# PDB_Sheet1.net
KiCad netlist of a schematic drawn in Altium Designer
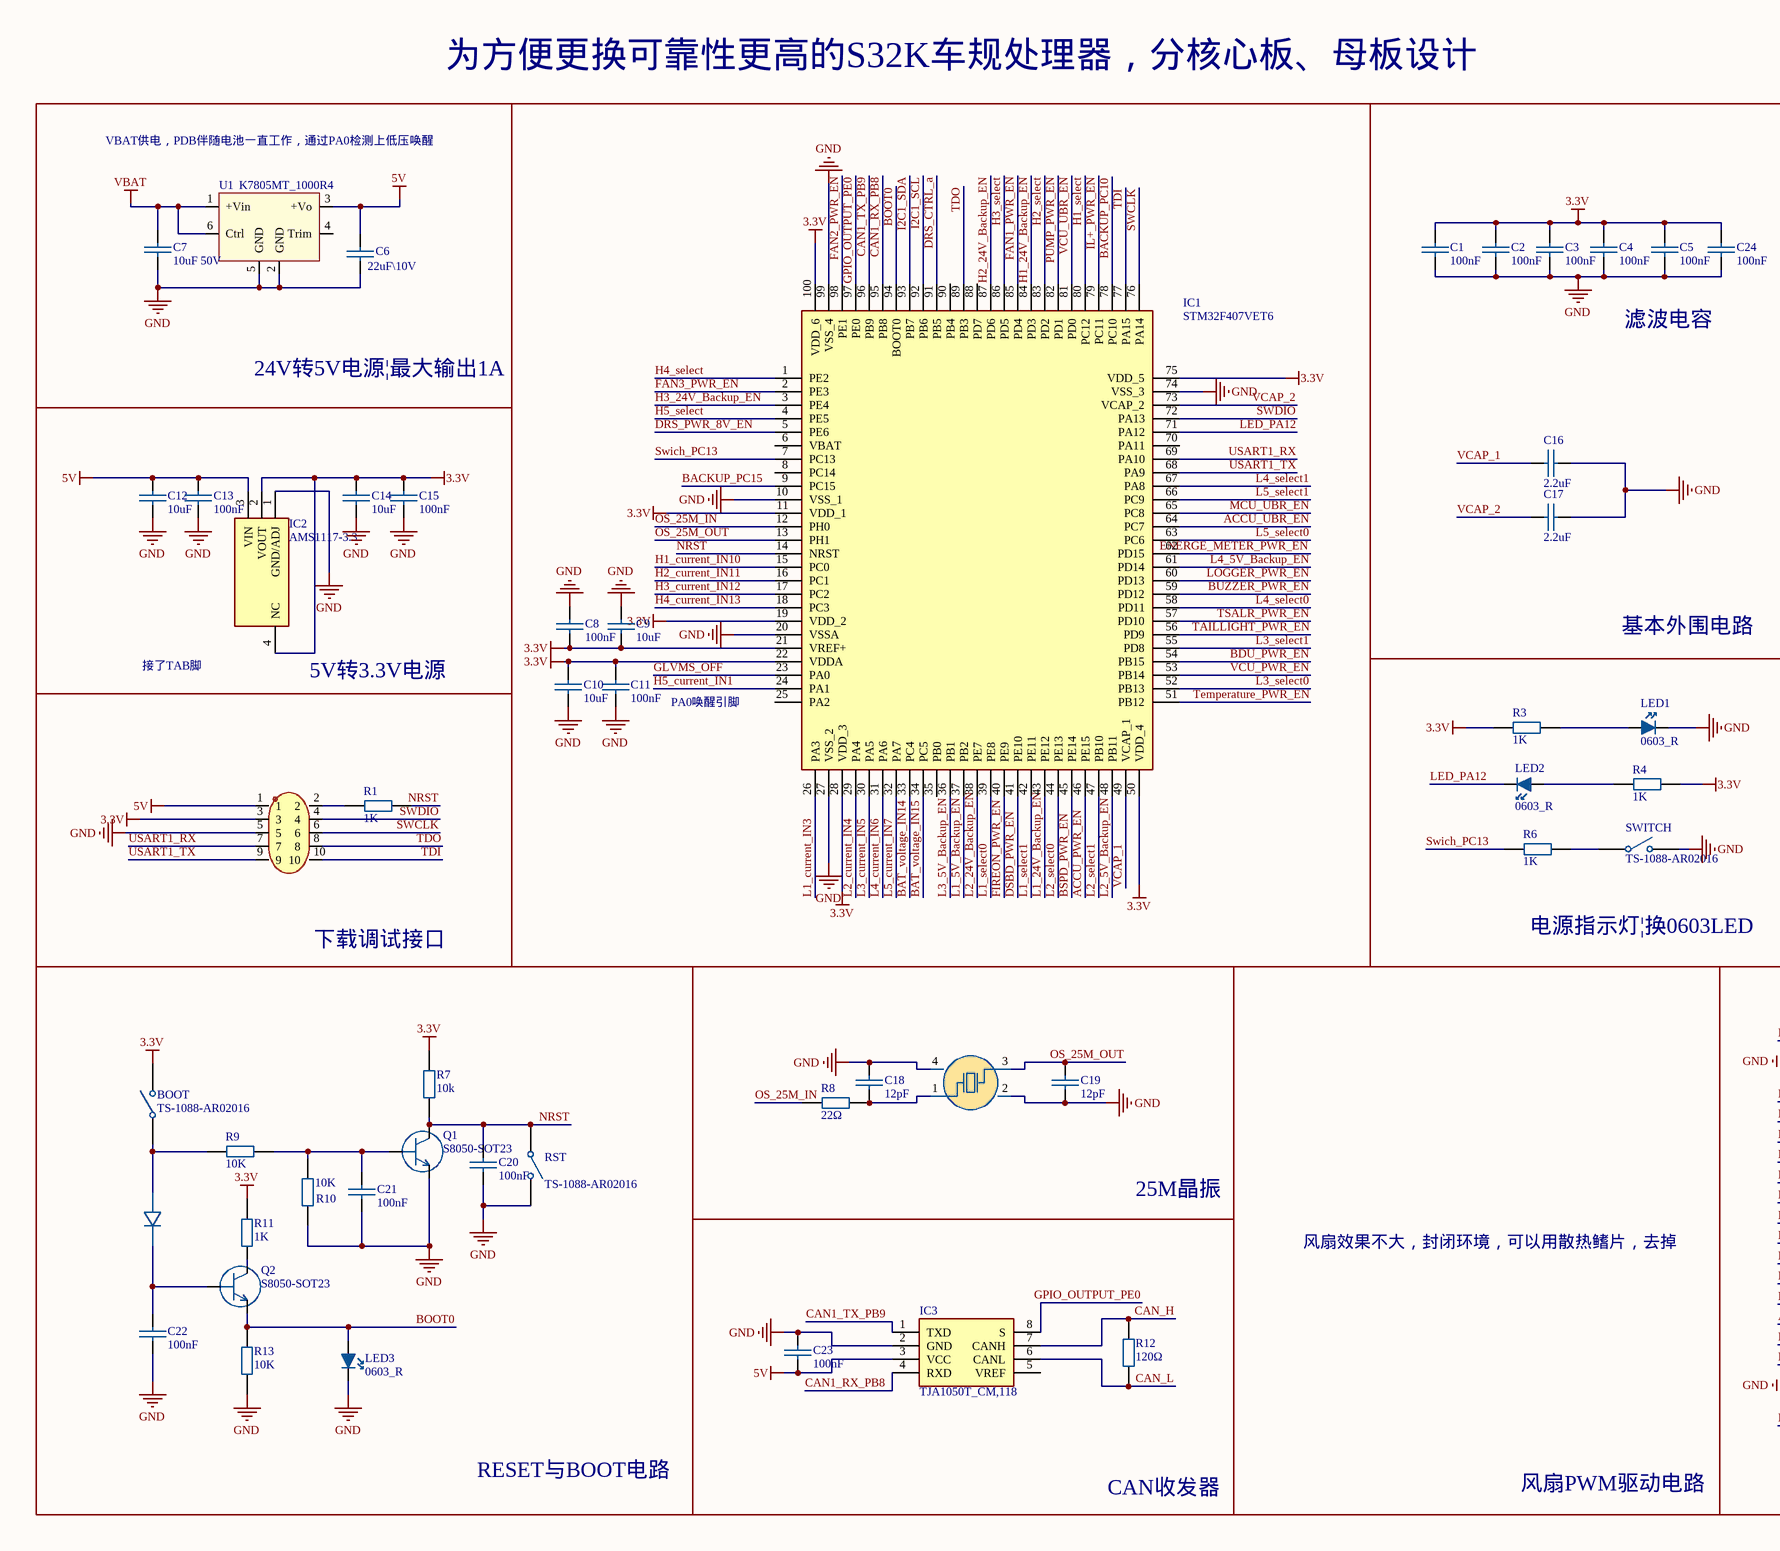
[diagram p0: PDB_Sheet1.SchDoc, left]
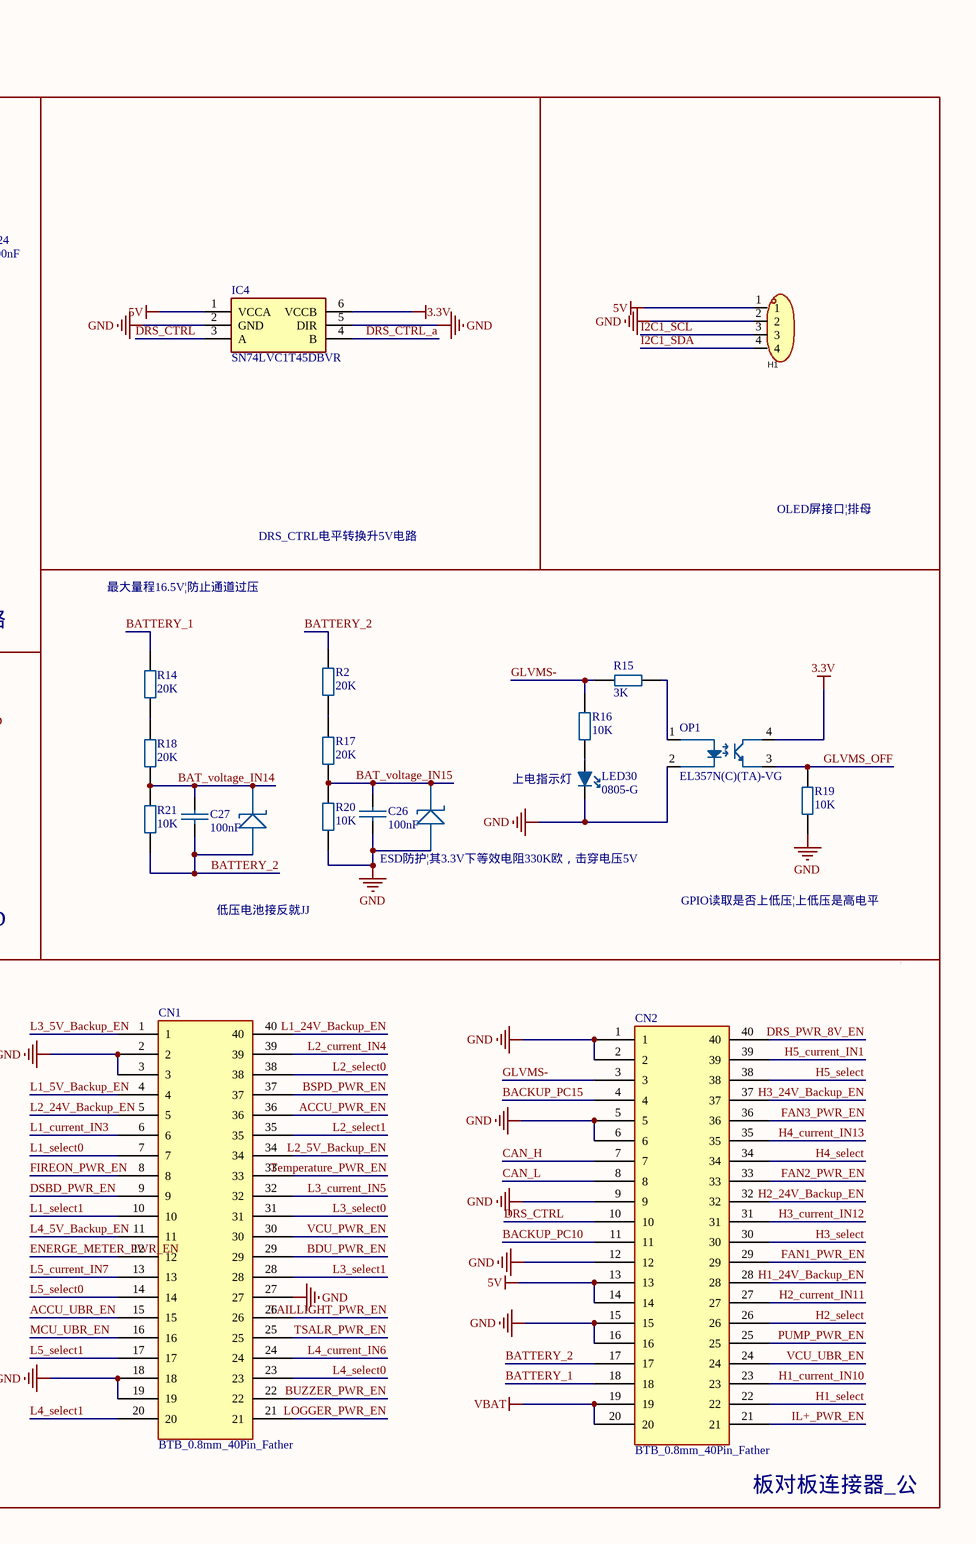
[diagram p1: PDB_Sheet1.SchDoc, right]

(export (version "E")
  (design (tool "Eeschema 10.0.6"))
  (components
    (comp (ref "BOOT")
      (value "TS-1088-AR02016")
      (footprint "SW-SMD_L3.9-W3.0-P4.45")
      (description "Switch")
      (libsource (lib "Switches") (part "TS-1088-AR02016"))
    )
    (comp (ref "C1")
      (value "100nF")
      (footprint "CAPC1608X08N__0603CAPUNPOLE")
      (description "Std MLCC Cap")
      (libsource (lib "ResistorCapacitorInductor") (part "SMD_MLCC"))
    )
    (comp (ref "C2")
      (value "100nF")
      (footprint "CAPC1608X08N__0603CAPUNPOLE")
      (description "Std MLCC Cap")
      (libsource (lib "ResistorCapacitorInductor") (part "SMD_MLCC"))
    )
    (comp (ref "C3")
      (value "100nF")
      (footprint "CAPC1608X08N__0603CAPUNPOLE")
      (description "Std MLCC Cap")
      (libsource (lib "ResistorCapacitorInductor") (part "SMD_MLCC"))
    )
    (comp (ref "C4")
      (value "100nF")
      (footprint "CAPC1608X08N__0603CAPUNPOLE")
      (description "Std MLCC Cap")
      (libsource (lib "ResistorCapacitorInductor") (part "SMD_MLCC"))
    )
    (comp (ref "C5")
      (value "100nF")
      (footprint "CAPC1608X08N__0603CAPUNPOLE")
      (description "Std MLCC Cap")
      (libsource (lib "ResistorCapacitorInductor") (part "SMD_MLCC"))
    )
    (comp (ref "C6")
      (value "22u~{F}10V")
      (footprint "CAPC1608X08N__0603CAPUNPOLE")
      (description "Std MLCC Cap")
      (libsource (lib "ResistorCapacitorInductor") (part "SMD_MLCC"))
    )
    (comp (ref "C7")
      (value "10uF 50V")
      (footprint "CAPC3216X16N_1206CAPUNPOLE")
      (description "Std MLCC Cap")
      (libsource (lib "ResistorCapacitorInductor") (part "SMD_MLCC"))
    )
    (comp (ref "C8")
      (value "100nF")
      (footprint "CAPC1608X08N__0603CAPUNPOLE")
      (description "Std MLCC Cap")
      (libsource (lib "ResistorCapacitorInductor") (part "SMD_MLCC"))
    )
    (comp (ref "C9")
      (value "10uF")
      (footprint "CAPC1608X08N__0603CAPUNPOLE")
      (description "Std MLCC Cap")
      (libsource (lib "ResistorCapacitorInductor") (part "SMD_MLCC"))
    )
    (comp (ref "C10")
      (value "10uF")
      (footprint "CAPC1608X08N__0603CAPUNPOLE")
      (description "Std MLCC Cap")
      (libsource (lib "ResistorCapacitorInductor") (part "SMD_MLCC"))
    )
    (comp (ref "C11")
      (value "100nF")
      (footprint "CAPC1608X08N__0603CAPUNPOLE")
      (description "Std MLCC Cap")
      (libsource (lib "ResistorCapacitorInductor") (part "SMD_MLCC"))
    )
    (comp (ref "C12")
      (value "10uF")
      (footprint "CAPC1608X08N__0603CAPUNPOLE")
      (description "Std MLCC Cap")
      (libsource (lib "ResistorCapacitorInductor") (part "SMD_MLCC"))
    )
    (comp (ref "C13")
      (value "100nF")
      (footprint "CAPC1608X08N__0603CAPUNPOLE")
      (description "Std MLCC Cap")
      (libsource (lib "ResistorCapacitorInductor") (part "SMD_MLCC"))
    )
    (comp (ref "C14")
      (value "10uF")
      (footprint "CAPC1608X08N__0603CAPUNPOLE")
      (description "Std MLCC Cap")
      (libsource (lib "ResistorCapacitorInductor") (part "SMD_MLCC"))
    )
    (comp (ref "C15")
      (value "100nF")
      (footprint "CAPC1608X08N__0603CAPUNPOLE")
      (description "Std MLCC Cap")
      (libsource (lib "ResistorCapacitorInductor") (part "SMD_MLCC"))
    )
    (comp (ref "C16")
      (value "2.2uF")
      (footprint "CAPC1608X08N__0603CAPUNPOLE")
      (description "Std MLCC Cap")
      (libsource (lib "ResistorCapacitorInductor") (part "SMD_MLCC"))
    )
    (comp (ref "C17")
      (value "2.2uF")
      (footprint "CAPC1608X08N__0603CAPUNPOLE")
      (description "Std MLCC Cap")
      (libsource (lib "ResistorCapacitorInductor") (part "SMD_MLCC"))
    )
    (comp (ref "C18")
      (value "12pF")
      (footprint "CAPC1608X08N__0603CAPUNPOLE")
      (description "Std MLCC Cap")
      (libsource (lib "ResistorCapacitorInductor") (part "SMD_MLCC"))
    )
    (comp (ref "C19")
      (value "12pF")
      (footprint "CAPC1608X08N__0603CAPUNPOLE")
      (description "Std MLCC Cap")
      (libsource (lib "ResistorCapacitorInductor") (part "SMD_MLCC"))
    )
    (comp (ref "C20")
      (value "100nF")
      (footprint "CAPC1608X08N__0603CAPUNPOLE")
      (description "Std MLCC Cap")
      (libsource (lib "ResistorCapacitorInductor") (part "SMD_MLCC"))
    )
    (comp (ref "C21")
      (value "100nF")
      (footprint "CAPC1608X08N__0603CAPUNPOLE")
      (description "Std MLCC Cap")
      (libsource (lib "ResistorCapacitorInductor") (part "SMD_MLCC"))
    )
    (comp (ref "C22")
      (value "100nF")
      (footprint "CAPC1608X08N__0603CAPUNPOLE")
      (description "Std MLCC Cap")
      (libsource (lib "ResistorCapacitorInductor") (part "SMD_MLCC"))
    )
    (comp (ref "C23")
      (value "100nF")
      (footprint "CAPC1608X08N__0603CAPUNPOLE")
      (description "Std MLCC Cap")
      (libsource (lib "ResistorCapacitorInductor") (part "SMD_MLCC"))
    )
    (comp (ref "C24")
      (value "100nF")
      (footprint "CAPC1608X08N__0603CAPUNPOLE")
      (description "Std MLCC Cap")
      (libsource (lib "ResistorCapacitorInductor") (part "SMD_MLCC"))
    )
    (comp (ref "C26")
      (value "100nF")
      (footprint "CAPC1608X08N__0603CAPUNPOLE")
      (description "Std MLCC Cap")
      (libsource (lib "ResistorCapacitorInductor") (part "SMD_MLCC"))
    )
    (comp (ref "C27")
      (value "100nF")
      (footprint "CAPC1608X08N__0603CAPUNPOLE")
      (description "Std MLCC Cap")
      (libsource (lib "ResistorCapacitorInductor") (part "SMD_MLCC"))
    )
    (comp (ref "CN1")
      (value "BTB_0.8mm_40Pin_Father")
      (footprint "BTB_0.8mm_40PIN_F")
      (libsource (lib "Connector") (part "BTB_0.8mm_40Pin_Father"))
    )
    (comp (ref "CN2")
      (value "BTB_0.8mm_40Pin_Father")
      (footprint "BTB_0.8mm_40PIN_F")
      (libsource (lib "Connector") (part "BTB_0.8mm_40Pin_Father"))
    )
    (comp (ref "D1")
      (value "1N4148WS_C2128")
      (footprint "SOD-323_L1.8-W1.3-LS2.5-RD")
      (fields (field (name "MANUFACTURER") "CJ(江苏长电/长晶)") (field (name "MANUFACTURER PART") "1N4148WS"))
      (libsource (lib "Diodes") (part "1N4148WS_C2128"))
    )
    (comp (ref "E1")
      (value "CESD3V3D3 YU")
      (footprint "SOD-323_L1.8-W1.3-LS2.5-RD")
      (description "极性:单向;反向截止电压(Vrwm):3.3V;击穿电压(VBR):5V;钳位电压(Vc)@Ipp:13V;")
      (fields (field (name "MANUFACTURER") "CJ(江苏长电/长晶)"))
      (libsource (lib "Diodes") (part "CESD3V3D3 YU"))
    )
    (comp (ref "E2")
      (value "CESD3V3D3 YU")
      (footprint "SOD-323_L1.8-W1.3-LS2.5-RD")
      (description "极性:单向;反向截止电压(Vrwm):3.3V;击穿电压(VBR):5V;钳位电压(Vc)@Ipp:13V;")
      (fields (field (name "MANUFACTURER") "CJ(江苏长电/长晶)"))
      (libsource (lib "Diodes") (part "CESD3V3D3 YU"))
    )
    (comp (ref "H1")
      (value "2.54-1*4P母")
      (footprint "HDR-TH_4P-P2.54-V-F")
      (description "立创编号：C2718488")
      (fields (field (name "MANUFACTURER") "BOOMELE(博穆精密)"))
      (libsource (lib "Connector") (part "2.54-1*4P母"))
    )
    (comp (ref "IC1")
      (value "STM32F407VET6")
      (footprint "QFP50P1600X1600X160-100N")
      (description "Integrated Circuit")
      (fields (field (name "MOUSER PART NUMBER") "511-STM32F407VET6"))
      (libsource (lib "*") (part "STM32F407VET6"))
    )
    (comp (ref "IC2")
      (value "AMS1117-3.3")
      (footprint "SOT229P700X180-4N")
      (description "Integrated Circuit")
      (libsource (lib "*") (part "AMS1117-3.3"))
    )
    (comp (ref "IC3")
      (value "TJA1050T_CM,118")
      (footprint "SOIC127P600X175-8N")
      (description "Integrated Circuit")
      (fields
        (field (name "MANUFACTURER_PART_NUMBER") "TJA1050T/CM,118")
        (field (name "MOUSER PART NUMBER") "771-TJA1050T/CM118")
      )
      (libsource (lib "*") (part "TJA1050T_CM,118"))
    )
    (comp (ref "IC4")
      (value "SN74LVC1T45DBVR")
      (footprint "SOT95P280X145-6N")
      (description "Integrated Circuit\r\n电平转换模块 立创编号：C7843")
      (fields (field (name "MOUSER PART NUMBER") "595-SN74LVC1T45DBVR"))
      (libsource (lib "GateDrivers") (part "SN74LVC1T45DBVR"))
    )
    (comp (ref "LED1")
      (value "0603_R")
      (footprint "LED0603-RD_RED")
      (description "Light Emitting Diode")
      (libsource (lib "Diodes") (part "LED"))
    )
    (comp (ref "LED2")
      (value "0603_R")
      (footprint "LED0603-RD_RED")
      (description "Light Emitting Diode")
      (libsource (lib "Diodes") (part "LED"))
    )
    (comp (ref "LED3")
      (value "0603_R")
      (footprint "LED0603-RD_RED")
      (description "Light Emitting Diode")
      (libsource (lib "Diodes") (part "LED"))
    )
    (comp (ref "LED30")
      (value "0805-G")
      (footprint "DIOC2012X11N__0805DIO")
      (description "Light Emitting Diode")
      (libsource (lib "Diodes") (part "LED"))
    )
    (comp (ref "OP1")
      (value "EL357N(C)(TA)-VG")
      (footprint "SOP-4-2.54mm")
      (description "No Description Available\r\n立创编号：C108648")
      (libsource (lib "Relay") (part "EL357N(C)(TA)-VG"))
    )
    (comp (ref "Q1")
      (value "S8050-SOT23")
      (footprint "SOT95P245X110-3N")
      (description "Jellybeam NPN")
      (libsource (lib "Transistor") (part "S8050"))
    )
    (comp (ref "Q2")
      (value "S8050-SOT23")
      (footprint "SOT95P245X110-3N")
      (description "Jellybeam NPN")
      (libsource (lib "Transistor") (part "S8050"))
    )
    (comp (ref "R1")
      (value "1K")
      (footprint "RESC3116X06N__1206RES")
      (description "Std Resistor")
      (libsource (lib "ResistorCapacitorInductor") (part "SMD_Resistor"))
    )
    (comp (ref "R2")
      (value "20K")
      (footprint "RESC1608X04N_0603RES")
      (description "Std Resistor")
      (libsource (lib "ResistorCapacitorInductor") (part "SMD_Resistor"))
    )
    (comp (ref "R3")
      (value "1K")
      (footprint "RESC1608X04N_0603RES")
      (description "Std Resistor")
      (libsource (lib "ResistorCapacitorInductor") (part "SMD_Resistor"))
    )
    (comp (ref "R4")
      (value "1K")
      (footprint "RESC1608X04N_0603RES")
      (description "Std Resistor")
      (libsource (lib "ResistorCapacitorInductor") (part "SMD_Resistor"))
    )
    (comp (ref "R6")
      (value "1K")
      (footprint "RESC1608X04N_0603RES")
      (description "Std Resistor")
      (libsource (lib "ResistorCapacitorInductor") (part "SMD_Resistor"))
    )
    (comp (ref "R7")
      (value "10k")
      (footprint "RESC1608X04N_0603RES")
      (description "Std Resistor")
      (libsource (lib "ResistorCapacitorInductor") (part "SMD_Resistor"))
    )
    (comp (ref "R8")
      (value "22Ω")
      (footprint "RESC1608X04N_0603RES")
      (description "Std Resistor")
      (libsource (lib "ResistorCapacitorInductor") (part "SMD_Resistor"))
    )
    (comp (ref "R9")
      (value "10K")
      (footprint "RESC1608X04N_0603RES")
      (description "Std Resistor")
      (libsource (lib "ResistorCapacitorInductor") (part "SMD_Resistor"))
    )
    (comp (ref "R10")
      (value "10K")
      (footprint "RESC1608X04N_0603RES")
      (description "Std Resistor")
      (libsource (lib "ResistorCapacitorInductor") (part "SMD_Resistor"))
    )
    (comp (ref "R11")
      (value "1K")
      (footprint "RESC1608X04N_0603RES")
      (description "Std Resistor")
      (libsource (lib "ResistorCapacitorInductor") (part "SMD_Resistor"))
    )
    (comp (ref "R12")
      (value "120Ω")
      (footprint "RESC1608X04N_0603RES")
      (description "Std Resistor")
      (libsource (lib "ResistorCapacitorInductor") (part "SMD_Resistor"))
    )
    (comp (ref "R13")
      (value "10K")
      (footprint "RESC1608X04N_0603RES")
      (description "Std Resistor")
      (libsource (lib "ResistorCapacitorInductor") (part "SMD_Resistor"))
    )
    (comp (ref "R14")
      (value "20K")
      (footprint "RESC1608X04N_0603RES")
      (description "Std Resistor")
      (libsource (lib "ResistorCapacitorInductor") (part "SMD_Resistor"))
    )
    (comp (ref "R15")
      (value "3K")
      (footprint "RESC1608X04N_0603RES")
      (description "Std Resistor")
      (libsource (lib "ResistorCapacitorInductor") (part "SMD_Resistor"))
    )
    (comp (ref "R16")
      (value "10K")
      (footprint "RESC1608X04N_0603RES")
      (description "Std Resistor")
      (libsource (lib "ResistorCapacitorInductor") (part "SMD_Resistor"))
    )
    (comp (ref "R17")
      (value "20K")
      (footprint "RESC1608X04N_0603RES")
      (description "Std Resistor")
      (libsource (lib "ResistorCapacitorInductor") (part "SMD_Resistor"))
    )
    (comp (ref "R18")
      (value "20K")
      (footprint "RESC1608X04N_0603RES")
      (description "Std Resistor")
      (libsource (lib "ResistorCapacitorInductor") (part "SMD_Resistor"))
    )
    (comp (ref "R19")
      (value "10K")
      (footprint "RESC1608X04N_0603RES")
      (description "Std Resistor")
      (libsource (lib "ResistorCapacitorInductor") (part "SMD_Resistor"))
    )
    (comp (ref "R20")
      (value "10K")
      (footprint "RESC1608X04N_0603RES")
      (description "Std Resistor")
      (libsource (lib "ResistorCapacitorInductor") (part "SMD_Resistor"))
    )
    (comp (ref "R21")
      (value "10K")
      (footprint "RESC1608X04N_0603RES")
      (description "Std Resistor")
      (libsource (lib "ResistorCapacitorInductor") (part "SMD_Resistor"))
    )
    (comp (ref "RST")
      (value "TS-1088-AR02016")
      (footprint "SW-SMD_L3.9-W3.0-P4.45")
      (description "Switch")
      (libsource (lib "Switches") (part "TS-1088-AR02016"))
    )
    (comp (ref "SWITCH")
      (value "TS-1088-AR02016")
      (footprint "SW-SMD_L3.9-W3.0-P4.45")
      (description "Switch")
      (libsource (lib "Switches") (part "TS-1088-AR02016"))
    )
    (comp (ref "U1")
      (value "K7805MT_1000R4")
      (footprint "K7805MT_500R4")
      (libsource (lib "DCDC_Converter") (part "K78052MT_1000R4"))
    )
    (comp (ref "U2")
      (value "ZX-PZ2.54-2-5PZZ")
      (footprint "HDR-TH_10P-P2.54-V-M-R2-C5-S2.54")
      (fields (field (name "MANUFACTURER") "Megastar(兆星)"))
      (libsource (lib "Connector") (part "ZX-PZ2.54-2-5PZZ"))
    )
    (comp (ref "X1")
      (value "X322525MOB4SI")
      (footprint "OSC-SMD_4P-L3.2-W2.5-BL")
      (description "频率:25MHz;频率公差:±10ppm;负载电容:12pF;")
      (fields (field (name "MANUFACTURER") "YXC(扬兴晶振)"))
      (libsource (lib "Crystals") (part "X322525MOB4SI"))
    )
  )
  (nets
    (net (code "1") (name "/ACCU_PWR_EN") (class "Default")
      (node (ref "CN1") (pin "36") (pinfunction "36_36") (pintype "passive"))
      (node (ref "IC1") (pin "46") (pinfunction "PE15_46") (pintype "passive"))
    )
    (net (code "2") (name "/ACCU_UBR_EN") (class "Default")
      (node (ref "CN1") (pin "15") (pinfunction "15_15") (pintype "passive"))
      (node (ref "IC1") (pin "64") (pinfunction "PC7_64") (pintype "passive"))
    )
    (net (code "3") (name "/BACKUP_PC10") (class "Default")
      (node (ref "CN2") (pin "11") (pinfunction "11_11") (pintype "passive"))
      (node (ref "IC1") (pin "78") (pinfunction "PC10_78") (pintype "passive"))
    )
    (net (code "4") (name "/BACKUP_PC15") (class "Default")
      (node (ref "CN2") (pin "4") (pinfunction "4_4") (pintype "passive"))
      (node (ref "IC1") (pin "9") (pinfunction "PC15_9") (pintype "passive"))
    )
    (net (code "5") (name "/BATTERY_1") (class "Default")
      (node (ref "CN2") (pin "18") (pinfunction "18_18") (pintype "passive"))
      (node (ref "R14") (pin "2") (pintype "passive"))
    )
    (net (code "6") (name "/BATTERY_2") (class "Default")
      (node (ref "C27") (pin "1") (pintype "passive"))
      (node (ref "CN2") (pin "17") (pinfunction "17_17") (pintype "passive"))
      (node (ref "E2") (pin "2") (pinfunction "2_2") (pintype "passive"))
      (node (ref "R2") (pin "2") (pintype "passive"))
      (node (ref "R21") (pin "2") (pintype "passive"))
    )
    (net (code "7") (name "/BAT_voltage_IN14") (class "Default")
      (node (ref "C27") (pin "2") (pintype "passive"))
      (node (ref "E2") (pin "1") (pinfunction "1_1") (pintype "passive"))
      (node (ref "IC1") (pin "33") (pinfunction "PC4_33") (pintype "passive"))
      (node (ref "R18") (pin "2") (pintype "passive"))
      (node (ref "R21") (pin "1") (pintype "passive"))
    )
    (net (code "8") (name "/BAT_voltage_IN15") (class "Default")
      (node (ref "C26") (pin "2") (pintype "passive"))
      (node (ref "E1") (pin "1") (pinfunction "1_1") (pintype "passive"))
      (node (ref "IC1") (pin "34") (pinfunction "PC5_34") (pintype "passive"))
      (node (ref "R17") (pin "2") (pintype "passive"))
      (node (ref "R20") (pin "1") (pintype "passive"))
    )
    (net (code "9") (name "/BDU_PWR_EN") (class "Default")
      (node (ref "CN1") (pin "29") (pinfunction "29_29") (pintype "passive"))
      (node (ref "IC1") (pin "54") (pinfunction "PB15_54") (pintype "passive"))
    )
    (net (code "10") (name "/BOOT0") (class "Default")
      (node (ref "IC1") (pin "94") (pinfunction "BOOT0_94") (pintype "passive"))
      (node (ref "LED3") (pin "2") (pintype "passive"))
      (node (ref "Q2") (pin "2") (pinfunction "Emitter_2") (pintype "passive"))
      (node (ref "R13") (pin "2") (pintype "passive"))
    )
    (net (code "11") (name "/BSPD_PWR_EN") (class "Default")
      (node (ref "CN1") (pin "37") (pinfunction "37_37") (pintype "passive"))
      (node (ref "IC1") (pin "45") (pinfunction "PE14_45") (pintype "passive"))
    )
    (net (code "12") (name "/BUZZER_PWR_EN") (class "Default")
      (node (ref "CN1") (pin "22") (pinfunction "22_22") (pintype "passive"))
      (node (ref "IC1") (pin "59") (pinfunction "PD12_59") (pintype "passive"))
    )
    (net (code "13") (name "/CAN1_RX_PB8") (class "Default")
      (node (ref "IC1") (pin "95") (pinfunction "PB8_95") (pintype "passive"))
      (node (ref "IC3") (pin "4") (pinfunction "RXD_4") (pintype "passive"))
    )
    (net (code "14") (name "/CAN1_TX_PB9") (class "Default")
      (node (ref "IC1") (pin "96") (pinfunction "PB9_96") (pintype "passive"))
      (node (ref "IC3") (pin "1") (pinfunction "TXD_1") (pintype "passive"))
    )
    (net (code "15") (name "/CAN_H") (class "Default")
      (node (ref "CN2") (pin "7") (pinfunction "7_7") (pintype "passive"))
      (node (ref "IC3") (pin "7") (pinfunction "CANH_7") (pintype "passive"))
      (node (ref "R12") (pin "2") (pintype "passive"))
    )
    (net (code "16") (name "/CAN_L") (class "Default")
      (node (ref "CN2") (pin "8") (pinfunction "8_8") (pintype "passive"))
      (node (ref "IC3") (pin "6") (pinfunction "CANL_6") (pintype "passive"))
      (node (ref "R12") (pin "1") (pintype "passive"))
    )
    (net (code "17") (name "/DRS_CTRL") (class "Default")
      (node (ref "CN2") (pin "10") (pinfunction "10_10") (pintype "passive"))
      (node (ref "IC4") (pin "3") (pinfunction "A_3") (pintype "passive"))
    )
    (net (code "18") (name "/DRS_CTRL_a") (class "Default")
      (node (ref "IC1") (pin "91") (pinfunction "PB5_91") (pintype "passive"))
      (node (ref "IC4") (pin "4") (pinfunction "B_4") (pintype "passive"))
    )
    (net (code "19") (name "/DRS_PWR_8V_EN") (class "Default")
      (node (ref "CN2") (pin "40") (pinfunction "40_40") (pintype "passive"))
      (node (ref "IC1") (pin "5") (pinfunction "PE6_5") (pintype "passive"))
    )
    (net (code "20") (name "/DSBD_PWR_EN") (class "Default")
      (node (ref "CN1") (pin "9") (pinfunction "9_9") (pintype "passive"))
      (node (ref "IC1") (pin "41") (pinfunction "PE10_41") (pintype "passive"))
    )
    (net (code "21") (name "/ENERGE_METER_PWR_EN") (class "Default")
      (node (ref "CN1") (pin "12") (pinfunction "12_12") (pintype "passive"))
      (node (ref "IC1") (pin "62") (pinfunction "PD15_62") (pintype "passive"))
    )
    (net (code "22") (name "/FAN1_PWR_EN") (class "Default")
      (node (ref "CN2") (pin "29") (pinfunction "29_29") (pintype "passive"))
      (node (ref "IC1") (pin "85") (pinfunction "PD4_85") (pintype "passive"))
    )
    (net (code "23") (name "/FAN2_PWR_EN") (class "Default")
      (node (ref "CN2") (pin "33") (pinfunction "33_33") (pintype "passive"))
      (node (ref "IC1") (pin "98") (pinfunction "PE1_98") (pintype "passive"))
    )
    (net (code "24") (name "/FAN3_PWR_EN") (class "Default")
      (node (ref "CN2") (pin "36") (pinfunction "36_36") (pintype "passive"))
      (node (ref "IC1") (pin "2") (pinfunction "PE3_2") (pintype "passive"))
    )
    (net (code "25") (name "/FIREON_PWR_EN") (class "Default")
      (node (ref "CN1") (pin "8") (pinfunction "8_8") (pintype "passive"))
      (node (ref "IC1") (pin "40") (pinfunction "PE9_40") (pintype "passive"))
    )
    (net (code "26") (name "/GLVMS-") (class "Default")
      (node (ref "CN2") (pin "3") (pinfunction "3_3") (pintype "passive"))
      (node (ref "R15") (pin "2") (pintype "passive"))
      (node (ref "R16") (pin "2") (pintype "passive"))
    )
    (net (code "27") (name "/GLVMS_OFF") (class "Default")
      (node (ref "IC1") (pin "23") (pinfunction "PA0_23") (pintype "passive"))
      (node (ref "OP1") (pin "3") (pinfunction "8_3") (pintype "passive"))
      (node (ref "R19") (pin "2") (pintype "passive"))
    )
    (net (code "28") (name "/GPIO_OUTPUT_PE0") (class "Default")
      (node (ref "IC1") (pin "97") (pinfunction "PE0_97") (pintype "passive"))
      (node (ref "IC3") (pin "8") (pinfunction "S_8") (pintype "passive"))
    )
    (net (code "29") (name "/H1_24V_Backup_EN") (class "Default")
      (node (ref "CN2") (pin "28") (pinfunction "28_28") (pintype "passive"))
      (node (ref "IC1") (pin "84") (pinfunction "PD3_84") (pintype "passive"))
    )
    (net (code "30") (name "/H1_current_IN10") (class "Default")
      (node (ref "CN2") (pin "23") (pinfunction "23_23") (pintype "passive"))
      (node (ref "IC1") (pin "15") (pinfunction "PC0_15") (pintype "passive"))
    )
    (net (code "31") (name "/H1_select") (class "Default")
      (node (ref "CN2") (pin "22") (pinfunction "22_22") (pintype "passive"))
      (node (ref "IC1") (pin "80") (pinfunction "PC12_80") (pintype "passive"))
    )
    (net (code "32") (name "/H2_24V_Backup_EN") (class "Default")
      (node (ref "CN2") (pin "32") (pinfunction "32_32") (pintype "passive"))
      (node (ref "IC1") (pin "87") (pinfunction "PD6_87") (pintype "passive"))
    )
    (net (code "33") (name "/H2_current_IN11") (class "Default")
      (node (ref "CN2") (pin "27") (pinfunction "27_27") (pintype "passive"))
      (node (ref "IC1") (pin "16") (pinfunction "PC1_16") (pintype "passive"))
    )
    (net (code "34") (name "/H2_select") (class "Default")
      (node (ref "CN2") (pin "26") (pinfunction "26_26") (pintype "passive"))
      (node (ref "IC1") (pin "83") (pinfunction "PD2_83") (pintype "passive"))
    )
    (net (code "35") (name "/H3_24V_Backup_EN") (class "Default")
      (node (ref "CN2") (pin "37") (pinfunction "37_37") (pintype "passive"))
      (node (ref "IC1") (pin "3") (pinfunction "PE4_3") (pintype "passive"))
    )
    (net (code "36") (name "/H3_current_IN12") (class "Default")
      (node (ref "CN2") (pin "31") (pinfunction "31_31") (pintype "passive"))
      (node (ref "IC1") (pin "17") (pinfunction "PC2_17") (pintype "passive"))
    )
    (net (code "37") (name "/H3_select") (class "Default")
      (node (ref "CN2") (pin "30") (pinfunction "30_30") (pintype "passive"))
      (node (ref "IC1") (pin "86") (pinfunction "PD5_86") (pintype "passive"))
    )
    (net (code "38") (name "/H4_current_IN13") (class "Default")
      (node (ref "CN2") (pin "35") (pinfunction "35_35") (pintype "passive"))
      (node (ref "IC1") (pin "18") (pinfunction "PC3_18") (pintype "passive"))
    )
    (net (code "39") (name "/H4_select") (class "Default")
      (node (ref "CN2") (pin "34") (pinfunction "34_34") (pintype "passive"))
      (node (ref "IC1") (pin "1") (pinfunction "PE2_1") (pintype "passive"))
    )
    (net (code "40") (name "/H5_current_IN1") (class "Default")
      (node (ref "CN2") (pin "39") (pinfunction "39_39") (pintype "passive"))
      (node (ref "IC1") (pin "24") (pinfunction "PA1_24") (pintype "passive"))
    )
    (net (code "41") (name "/H5_select") (class "Default")
      (node (ref "CN2") (pin "38") (pinfunction "38_38") (pintype "passive"))
      (node (ref "IC1") (pin "4") (pinfunction "PE5_4") (pintype "passive"))
    )
    (net (code "42") (name "/I2C1_SCL") (class "Default")
      (node (ref "H1") (pin "3") (pinfunction "3_3") (pintype "passive"))
      (node (ref "IC1") (pin "92") (pinfunction "PB6_92") (pintype "passive"))
    )
    (net (code "43") (name "/I2C1_SDA") (class "Default")
      (node (ref "H1") (pin "4") (pinfunction "4_4") (pintype "passive"))
      (node (ref "IC1") (pin "93") (pinfunction "PB7_93") (pintype "passive"))
    )
    (net (code "44") (name "/IL+_PWR_EN") (class "Default")
      (node (ref "CN2") (pin "21") (pinfunction "21_21") (pintype "passive"))
      (node (ref "IC1") (pin "79") (pinfunction "PC11_79") (pintype "passive"))
    )
    (net (code "45") (name "/L1_5V_Backup_EN") (class "Default")
      (node (ref "CN1") (pin "4") (pinfunction "4_4") (pintype "passive"))
      (node (ref "IC1") (pin "37") (pinfunction "PB2_37") (pintype "passive"))
    )
    (net (code "46") (name "/L1_24V_Backup_EN") (class "Default")
      (node (ref "CN1") (pin "40") (pinfunction "40_40") (pintype "passive"))
      (node (ref "IC1") (pin "43") (pinfunction "PE12_43") (pintype "passive"))
    )
    (net (code "47") (name "/L1_current_IN3") (class "Default")
      (node (ref "CN1") (pin "6") (pinfunction "6_6") (pintype "passive"))
      (node (ref "IC1") (pin "26") (pinfunction "PA3_26") (pintype "passive"))
    )
    (net (code "48") (name "/L1_select0") (class "Default")
      (node (ref "CN1") (pin "7") (pinfunction "7_7") (pintype "passive"))
      (node (ref "IC1") (pin "39") (pinfunction "PE8_39") (pintype "passive"))
    )
    (net (code "49") (name "/L1_select1") (class "Default")
      (node (ref "CN1") (pin "10") (pinfunction "10_10") (pintype "passive"))
      (node (ref "IC1") (pin "42") (pinfunction "PE11_42") (pintype "passive"))
    )
    (net (code "50") (name "/L2_5V_Backup_EN") (class "Default")
      (node (ref "CN1") (pin "34") (pinfunction "34_34") (pintype "passive"))
      (node (ref "IC1") (pin "48") (pinfunction "PB11_48") (pintype "passive"))
    )
    (net (code "51") (name "/L2_24V_Backup_EN") (class "Default")
      (node (ref "CN1") (pin "5") (pinfunction "5_5") (pintype "passive"))
      (node (ref "IC1") (pin "38") (pinfunction "PE7_38") (pintype "passive"))
    )
    (net (code "52") (name "/L2_current_IN4") (class "Default")
      (node (ref "CN1") (pin "39") (pinfunction "39_39") (pintype "passive"))
      (node (ref "IC1") (pin "29") (pinfunction "PA4_29") (pintype "passive"))
    )
    (net (code "53") (name "/L2_select0") (class "Default")
      (node (ref "CN1") (pin "38") (pinfunction "38_38") (pintype "passive"))
      (node (ref "IC1") (pin "44") (pinfunction "PE13_44") (pintype "passive"))
    )
    (net (code "54") (name "/L2_select1") (class "Default")
      (node (ref "CN1") (pin "35") (pinfunction "35_35") (pintype "passive"))
      (node (ref "IC1") (pin "47") (pinfunction "PB10_47") (pintype "passive"))
    )
    (net (code "55") (name "/L3_5V_Backup_EN") (class "Default")
      (node (ref "CN1") (pin "1") (pinfunction "1_1") (pintype "passive"))
      (node (ref "IC1") (pin "36") (pinfunction "PB1_36") (pintype "passive"))
    )
    (net (code "56") (name "/L3_current_IN5") (class "Default")
      (node (ref "CN1") (pin "32") (pinfunction "32_32") (pintype "passive"))
      (node (ref "IC1") (pin "30") (pinfunction "PA5_30") (pintype "passive"))
    )
    (net (code "57") (name "/L3_select0") (class "Default")
      (node (ref "CN1") (pin "31") (pinfunction "31_31") (pintype "passive"))
      (node (ref "IC1") (pin "52") (pinfunction "PB13_52") (pintype "passive"))
    )
    (net (code "58") (name "/L3_select1") (class "Default")
      (node (ref "CN1") (pin "28") (pinfunction "28_28") (pintype "passive"))
      (node (ref "IC1") (pin "55") (pinfunction "PD8_55") (pintype "passive"))
    )
    (net (code "59") (name "/L4_5V_Backup_EN") (class "Default")
      (node (ref "CN1") (pin "11") (pinfunction "11_11") (pintype "passive"))
      (node (ref "IC1") (pin "61") (pinfunction "PD14_61") (pintype "passive"))
    )
    (net (code "60") (name "/L4_current_IN6") (class "Default")
      (node (ref "CN1") (pin "24") (pinfunction "24_24") (pintype "passive"))
      (node (ref "IC1") (pin "31") (pinfunction "PA6_31") (pintype "passive"))
    )
    (net (code "61") (name "/L4_select0") (class "Default")
      (node (ref "CN1") (pin "23") (pinfunction "23_23") (pintype "passive"))
      (node (ref "IC1") (pin "58") (pinfunction "PD11_58") (pintype "passive"))
    )
    (net (code "62") (name "/L4_select1") (class "Default")
      (node (ref "CN1") (pin "20") (pinfunction "20_20") (pintype "passive"))
      (node (ref "IC1") (pin "67") (pinfunction "PA8_67") (pintype "passive"))
    )
    (net (code "63") (name "/L5_current_IN7") (class "Default")
      (node (ref "CN1") (pin "13") (pinfunction "13_13") (pintype "passive"))
      (node (ref "IC1") (pin "32") (pinfunction "PA7_32") (pintype "passive"))
    )
    (net (code "64") (name "/L5_select0") (class "Default")
      (node (ref "CN1") (pin "14") (pinfunction "14_14") (pintype "passive"))
      (node (ref "IC1") (pin "63") (pinfunction "PC6_63") (pintype "passive"))
    )
    (net (code "65") (name "/L5_select1") (class "Default")
      (node (ref "CN1") (pin "17") (pinfunction "17_17") (pintype "passive"))
      (node (ref "IC1") (pin "66") (pinfunction "PC9_66") (pintype "passive"))
    )
    (net (code "66") (name "/LED_PA12") (class "Default")
      (node (ref "IC1") (pin "71") (pinfunction "PA12_71") (pintype "passive"))
      (node (ref "LED2") (pin "1") (pintype "passive"))
    )
    (net (code "67") (name "/LOGGER_PWR_EN") (class "Default")
      (node (ref "CN1") (pin "21") (pinfunction "21_21") (pintype "passive"))
      (node (ref "IC1") (pin "60") (pinfunction "PD13_60") (pintype "passive"))
    )
    (net (code "68") (name "/MCU_UBR_EN") (class "Default")
      (node (ref "CN1") (pin "16") (pinfunction "16_16") (pintype "passive"))
      (node (ref "IC1") (pin "65") (pinfunction "PC8_65") (pintype "passive"))
    )
    (net (code "69") (name "/NRST") (class "Default")
      (node (ref "C20") (pin "2") (pintype "passive"))
      (node (ref "IC1") (pin "14") (pinfunction "NRST_14") (pintype "passive"))
      (node (ref "Q1") (pin "3") (pinfunction "Collector_3") (pintype "passive"))
      (node (ref "R1") (pin "2") (pintype "passive"))
      (node (ref "R7") (pin "1") (pintype "passive"))
      (node (ref "RST") (pin "1") (pinfunction "COMMON_1") (pintype "passive"))
    )
    (net (code "70") (name "/OS_25M_IN") (class "Default")
      (node (ref "IC1") (pin "12") (pinfunction "PH0_12") (pintype "passive"))
      (node (ref "R8") (pin "1") (pintype "passive"))
    )
    (net (code "71") (name "/OS_25M_OUT") (class "Default")
      (node (ref "C19") (pin "2") (pintype "passive"))
      (node (ref "IC1") (pin "13") (pinfunction "PH1_13") (pintype "passive"))
      (node (ref "X1") (pin "3") (pinfunction "OSC2_3") (pintype "passive"))
    )
    (net (code "72") (name "/PUMP_PWR_EN") (class "Default")
      (node (ref "CN2") (pin "25") (pinfunction "25_25") (pintype "passive"))
      (node (ref "IC1") (pin "82") (pinfunction "PD1_82") (pintype "passive"))
    )
    (net (code "73") (name "/SWCLK") (class "Default")
      (node (ref "IC1") (pin "76") (pinfunction "PA14_76") (pintype "passive"))
      (node (ref "U2") (pin "6") (pinfunction "6_6") (pintype "passive"))
    )
    (net (code "74") (name "/SWDIO") (class "Default")
      (node (ref "IC1") (pin "72") (pinfunction "PA13_72") (pintype "passive"))
      (node (ref "U2") (pin "4") (pinfunction "4_4") (pintype "passive"))
    )
    (net (code "75") (name "/Swich_PC13") (class "Default")
      (node (ref "IC1") (pin "7") (pinfunction "PC13_7") (pintype "passive"))
      (node (ref "R6") (pin "1") (pintype "passive"))
    )
    (net (code "76") (name "/TAILLIGHT_PWR_EN") (class "Default")
      (node (ref "CN1") (pin "26") (pinfunction "26_26") (pintype "passive"))
      (node (ref "IC1") (pin "56") (pinfunction "PD9_56") (pintype "passive"))
    )
    (net (code "77") (name "/TDI") (class "Default")
      (node (ref "IC1") (pin "77") (pinfunction "PA15_77") (pintype "passive"))
      (node (ref "U2") (pin "10") (pinfunction "10_10") (pintype "passive"))
    )
    (net (code "78") (name "/TDO") (class "Default")
      (node (ref "IC1") (pin "89") (pinfunction "PB3_89") (pintype "passive"))
      (node (ref "U2") (pin "8") (pinfunction "8_8") (pintype "passive"))
    )
    (net (code "79") (name "/TSALR_PWR_EN") (class "Default")
      (node (ref "CN1") (pin "25") (pinfunction "25_25") (pintype "passive"))
      (node (ref "IC1") (pin "57") (pinfunction "PD10_57") (pintype "passive"))
    )
    (net (code "80") (name "/Temperature_PWR_EN") (class "Default")
      (node (ref "CN1") (pin "33") (pinfunction "33_33") (pintype "passive"))
      (node (ref "IC1") (pin "51") (pinfunction "PB12_51") (pintype "passive"))
    )
    (net (code "81") (name "/USART1_RX") (class "Default")
      (node (ref "IC1") (pin "69") (pinfunction "PA10_69") (pintype "passive"))
      (node (ref "U2") (pin "7") (pinfunction "7_7") (pintype "passive"))
    )
    (net (code "82") (name "/USART1_TX") (class "Default")
      (node (ref "IC1") (pin "68") (pinfunction "PA9_68") (pintype "passive"))
      (node (ref "U2") (pin "9") (pinfunction "9_9") (pintype "passive"))
    )
    (net (code "83") (name "/VCAP_1") (class "Default")
      (node (ref "C16") (pin "1") (pintype "passive"))
      (node (ref "IC1") (pin "49") (pinfunction "VCAP_1_49") (pintype "passive"))
    )
    (net (code "84") (name "/VCAP_2") (class "Default")
      (node (ref "C17") (pin "1") (pintype "passive"))
      (node (ref "IC1") (pin "73") (pinfunction "VCAP_2_73") (pintype "passive"))
    )
    (net (code "85") (name "/VCU_PWR_EN") (class "Default")
      (node (ref "CN1") (pin "30") (pinfunction "30_30") (pintype "passive"))
      (node (ref "IC1") (pin "53") (pinfunction "PB14_53") (pintype "passive"))
    )
    (net (code "86") (name "/VCU_UBR_EN") (class "Default")
      (node (ref "CN2") (pin "24") (pinfunction "24_24") (pintype "passive"))
      (node (ref "IC1") (pin "81") (pinfunction "PD0_81") (pintype "passive"))
    )
    (net (code "87") (name "3.3V") (class "Default")
      (node (ref "BOOT") (pin "2") (pinfunction "NO_2") (pintype "passive"))
      (node (ref "C1") (pin "2") (pintype "passive"))
      (node (ref "C10") (pin "2") (pintype "passive"))
      (node (ref "C11") (pin "2") (pintype "passive"))
      (node (ref "C14") (pin "2") (pintype "passive"))
      (node (ref "C15") (pin "2") (pintype "passive"))
      (node (ref "C2") (pin "2") (pintype "passive"))
      (node (ref "C24") (pin "2") (pintype "passive"))
      (node (ref "C3") (pin "2") (pintype "passive"))
      (node (ref "C4") (pin "2") (pintype "passive"))
      (node (ref "C5") (pin "2") (pintype "passive"))
      (node (ref "C8") (pin "2") (pintype "passive"))
      (node (ref "C9") (pin "2") (pintype "passive"))
      (node (ref "IC1") (pin "100") (pinfunction "VDD_6_100") (pintype "passive"))
      (node (ref "IC1") (pin "11") (pinfunction "VDD_1_11") (pintype "passive"))
      (node (ref "IC1") (pin "19") (pinfunction "VDD_2_19") (pintype "passive"))
      (node (ref "IC1") (pin "21") (pinfunction "VREF+_21") (pintype "passive"))
      (node (ref "IC1") (pin "22") (pinfunction "VDDA_22") (pintype "passive"))
      (node (ref "IC1") (pin "28") (pinfunction "VDD_3_28") (pintype "passive"))
      (node (ref "IC1") (pin "50") (pinfunction "VDD_4_50") (pintype "passive"))
      (node (ref "IC1") (pin "75") (pinfunction "VDD_5_75") (pintype "passive"))
      (node (ref "IC2") (pin "2") (pinfunction "VOUT_2") (pintype "passive"))
      (node (ref "IC2") (pin "4") (pinfunction "NC_4") (pintype "passive"))
      (node (ref "IC4") (pin "6") (pinfunction "VCCB_6") (pintype "passive"))
      (node (ref "OP1") (pin "4") (pinfunction "9_4") (pintype "passive"))
      (node (ref "R11") (pin "2") (pintype "passive"))
      (node (ref "R3") (pin "1") (pintype "passive"))
      (node (ref "R4") (pin "2") (pintype "passive"))
      (node (ref "R7") (pin "2") (pintype "passive"))
      (node (ref "U2") (pin "3") (pinfunction "3_3") (pintype "passive"))
    )
    (net (code "88") (name "5V") (class "Default")
      (node (ref "C12") (pin "2") (pintype "passive"))
      (node (ref "C13") (pin "2") (pintype "passive"))
      (node (ref "C23") (pin "2") (pintype "passive"))
      (node (ref "C6") (pin "2") (pintype "passive"))
      (node (ref "CN2") (pin "13") (pinfunction "13_13") (pintype "passive"))
      (node (ref "CN2") (pin "14") (pinfunction "14_14") (pintype "passive"))
      (node (ref "H1") (pin "1") (pinfunction "1_1") (pintype "passive"))
      (node (ref "IC2") (pin "3") (pinfunction "VIN_3") (pintype "passive"))
      (node (ref "IC3") (pin "3") (pinfunction "VCC_3") (pintype "passive"))
      (node (ref "IC4") (pin "1") (pinfunction "VCCA_1") (pintype "passive"))
      (node (ref "U1") (pin "3") (pinfunction "+Vo_3") (pintype "passive"))
      (node (ref "U2") (pin "1") (pinfunction "1_1") (pintype "passive"))
    )
    (net (code "89") (name "GND") (class "Default")
      (node (ref "C1") (pin "1") (pintype "passive"))
      (node (ref "C10") (pin "1") (pintype "passive"))
      (node (ref "C11") (pin "1") (pintype "passive"))
      (node (ref "C12") (pin "1") (pintype "passive"))
      (node (ref "C13") (pin "1") (pintype "passive"))
      (node (ref "C14") (pin "1") (pintype "passive"))
      (node (ref "C15") (pin "1") (pintype "passive"))
      (node (ref "C16") (pin "2") (pintype "passive"))
      (node (ref "C17") (pin "2") (pintype "passive"))
      (node (ref "C18") (pin "2") (pintype "passive"))
      (node (ref "C19") (pin "1") (pintype "passive"))
      (node (ref "C2") (pin "1") (pintype "passive"))
      (node (ref "C20") (pin "1") (pintype "passive"))
      (node (ref "C21") (pin "1") (pintype "passive"))
      (node (ref "C22") (pin "1") (pintype "passive"))
      (node (ref "C23") (pin "1") (pintype "passive"))
      (node (ref "C24") (pin "1") (pintype "passive"))
      (node (ref "C26") (pin "1") (pintype "passive"))
      (node (ref "C3") (pin "1") (pintype "passive"))
      (node (ref "C4") (pin "1") (pintype "passive"))
      (node (ref "C5") (pin "1") (pintype "passive"))
      (node (ref "C6") (pin "1") (pintype "passive"))
      (node (ref "C7") (pin "1") (pintype "passive"))
      (node (ref "C8") (pin "1") (pintype "passive"))
      (node (ref "C9") (pin "1") (pintype "passive"))
      (node (ref "CN1") (pin "18") (pinfunction "18_18") (pintype "passive"))
      (node (ref "CN1") (pin "19") (pinfunction "19_19") (pintype "passive"))
      (node (ref "CN1") (pin "2") (pinfunction "2_2") (pintype "passive"))
      (node (ref "CN1") (pin "27") (pinfunction "27_27") (pintype "passive"))
      (node (ref "CN1") (pin "3") (pinfunction "3_3") (pintype "passive"))
      (node (ref "CN2") (pin "1") (pinfunction "1_1") (pintype "passive"))
      (node (ref "CN2") (pin "12") (pinfunction "12_12") (pintype "passive"))
      (node (ref "CN2") (pin "15") (pinfunction "15_15") (pintype "passive"))
      (node (ref "CN2") (pin "16") (pinfunction "16_16") (pintype "passive"))
      (node (ref "CN2") (pin "2") (pinfunction "2_2") (pintype "passive"))
      (node (ref "CN2") (pin "5") (pinfunction "5_5") (pintype "passive"))
      (node (ref "CN2") (pin "6") (pinfunction "6_6") (pintype "passive"))
      (node (ref "CN2") (pin "9") (pinfunction "9_9") (pintype "passive"))
      (node (ref "E1") (pin "2") (pinfunction "2_2") (pintype "passive"))
      (node (ref "H1") (pin "2") (pinfunction "2_2") (pintype "passive"))
      (node (ref "IC1") (pin "10") (pinfunction "VSS_1_10") (pintype "passive"))
      (node (ref "IC1") (pin "20") (pinfunction "VSSA_20") (pintype "passive"))
      (node (ref "IC1") (pin "27") (pinfunction "VSS_2_27") (pintype "passive"))
      (node (ref "IC1") (pin "74") (pinfunction "VSS_3_74") (pintype "passive"))
      (node (ref "IC1") (pin "99") (pinfunction "VSS_4_99") (pintype "passive"))
      (node (ref "IC2") (pin "1") (pinfunction "GND/ADJ_1") (pintype "passive"))
      (node (ref "IC3") (pin "2") (pinfunction "GND_2") (pintype "passive"))
      (node (ref "IC4") (pin "2") (pinfunction "GND_2") (pintype "passive"))
      (node (ref "IC4") (pin "5") (pinfunction "DIR_5") (pintype "passive"))
      (node (ref "LED1") (pin "1") (pintype "passive"))
      (node (ref "LED3") (pin "1") (pintype "passive"))
      (node (ref "LED30") (pin "1") (pintype "passive"))
      (node (ref "OP1") (pin "2") (pinfunction "7_2") (pintype "passive"))
      (node (ref "Q1") (pin "2") (pinfunction "Emitter_2") (pintype "passive"))
      (node (ref "R10") (pin "1") (pintype "passive"))
      (node (ref "R13") (pin "1") (pintype "passive"))
      (node (ref "R19") (pin "1") (pintype "passive"))
      (node (ref "R20") (pin "2") (pintype "passive"))
      (node (ref "RST") (pin "2") (pinfunction "NO_2") (pintype "passive"))
      (node (ref "SWITCH") (pin "2") (pinfunction "NO_2") (pintype "passive"))
      (node (ref "U1") (pin "2") (pinfunction "GND_2") (pintype "passive"))
      (node (ref "U1") (pin "5") (pinfunction "GND_5") (pintype "passive"))
      (node (ref "U2") (pin "5") (pinfunction "5_5") (pintype "passive"))
      (node (ref "X1") (pin "2") (pinfunction "GND_2") (pintype "passive"))
      (node (ref "X1") (pin "4") (pinfunction "GND_4") (pintype "passive"))
    )
    (net (code "90") (name "Net-(BOOT-COMMON)") (class "Default")
      (node (ref "BOOT") (pin "1") (pinfunction "COMMON_1") (pintype "passive"))
      (node (ref "D1") (pin "2") (pinfunction "A_2") (pintype "passive"))
      (node (ref "R9") (pin "1") (pintype "passive"))
    )
    (net (code "91") (name "Net-(D1-K)") (class "Default")
      (node (ref "C22") (pin "2") (pintype "passive"))
      (node (ref "D1") (pin "1") (pinfunction "K_1") (pintype "passive"))
      (node (ref "Q2") (pin "1") (pinfunction "Base_1") (pintype "passive"))
    )
    (net (code "92") (name "Net-(LED1-Pad2)") (class "Default")
      (node (ref "LED1") (pin "2") (pintype "passive"))
      (node (ref "R3") (pin "2") (pintype "passive"))
    )
    (net (code "93") (name "Net-(LED2-Pad2)") (class "Default")
      (node (ref "LED2") (pin "2") (pintype "passive"))
      (node (ref "R4") (pin "1") (pintype "passive"))
    )
    (net (code "94") (name "Net-(LED30-Pad2)") (class "Default")
      (node (ref "LED30") (pin "2") (pintype "passive"))
      (node (ref "R16") (pin "1") (pintype "passive"))
    )
    (net (code "95") (name "Net-(OP1-6)") (class "Default")
      (node (ref "OP1") (pin "1") (pinfunction "6_1") (pintype "passive"))
      (node (ref "R15") (pin "1") (pintype "passive"))
    )
    (net (code "96") (name "Net-(Q1-Base)") (class "Default")
      (node (ref "C21") (pin "2") (pintype "passive"))
      (node (ref "Q1") (pin "1") (pinfunction "Base_1") (pintype "passive"))
      (node (ref "R10") (pin "2") (pintype "passive"))
      (node (ref "R9") (pin "2") (pintype "passive"))
    )
    (net (code "97") (name "Net-(Q2-Collector)") (class "Default")
      (node (ref "Q2") (pin "3") (pinfunction "Collector_3") (pintype "passive"))
      (node (ref "R11") (pin "1") (pintype "passive"))
    )
    (net (code "98") (name "Net-(R1-Pad1)") (class "Default")
      (node (ref "R1") (pin "1") (pintype "passive"))
      (node (ref "U2") (pin "2") (pinfunction "2_2") (pintype "passive"))
    )
    (net (code "99") (name "Net-(R14-Pad1)") (class "Default")
      (node (ref "R14") (pin "1") (pintype "passive"))
      (node (ref "R18") (pin "1") (pintype "passive"))
    )
    (net (code "100") (name "Net-(R17-Pad1)") (class "Default")
      (node (ref "R17") (pin "1") (pintype "passive"))
      (node (ref "R2") (pin "1") (pintype "passive"))
    )
    (net (code "101") (name "Net-(SWITCH-COMMON)") (class "Default")
      (node (ref "R6") (pin "2") (pintype "passive"))
      (node (ref "SWITCH") (pin "1") (pinfunction "COMMON_1") (pintype "passive"))
    )
    (net (code "102") (name "Net-(X1-OSC1)") (class "Default")
      (node (ref "C18") (pin "1") (pintype "passive"))
      (node (ref "R8") (pin "2") (pintype "passive"))
      (node (ref "X1") (pin "1") (pinfunction "OSC1_1") (pintype "passive"))
    )
    (net (code "103") (name "VBAT") (class "Default")
      (node (ref "C7") (pin "2") (pintype "passive"))
      (node (ref "CN2") (pin "19") (pinfunction "19_19") (pintype "passive"))
      (node (ref "CN2") (pin "20") (pinfunction "20_20") (pintype "passive"))
      (node (ref "U1") (pin "1") (pinfunction "+Vin_1") (pintype "passive"))
      (node (ref "U1") (pin "6") (pinfunction "Ctrl_6") (pintype "passive"))
    )
    (net (code "104") (name "unconnected-(IC1-PA2-Pad25)") (class "Default")
      (node (ref "IC1") (pin "25") (pinfunction "PA2_25") (pintype "passive"))
    )
    (net (code "105") (name "unconnected-(IC1-PA11-Pad70)") (class "Default")
      (node (ref "IC1") (pin "70") (pinfunction "PA11_70") (pintype "passive"))
    )
    (net (code "106") (name "unconnected-(IC1-PB0-Pad35)") (class "Default")
      (node (ref "IC1") (pin "35") (pinfunction "PB0_35") (pintype "passive"))
    )
    (net (code "107") (name "unconnected-(IC1-PB4-Pad90)") (class "Default")
      (node (ref "IC1") (pin "90") (pinfunction "PB4_90") (pintype "passive"))
    )
    (net (code "108") (name "unconnected-(IC1-PC14-Pad8)") (class "Default")
      (node (ref "IC1") (pin "8") (pinfunction "PC14_8") (pintype "passive"))
    )
    (net (code "109") (name "unconnected-(IC1-PD7-Pad88)") (class "Default")
      (node (ref "IC1") (pin "88") (pinfunction "PD7_88") (pintype "passive"))
    )
    (net (code "110") (name "unconnected-(IC1-VBAT-Pad6)") (class "Default")
      (node (ref "IC1") (pin "6") (pinfunction "VBAT_6") (pintype "passive"))
    )
    (net (code "111") (name "unconnected-(IC3-VREF-Pad5)") (class "Default")
      (node (ref "IC3") (pin "5") (pinfunction "VREF_5") (pintype "passive"))
    )
    (net (code "112") (name "unconnected-(U1-Trim-Pad4)") (class "Default")
      (node (ref "U1") (pin "4") (pinfunction "Trim_4") (pintype "passive"))
    )
  )
)
